# Sheet1.net
KiCad netlist of a schematic drawn in Altium Designer
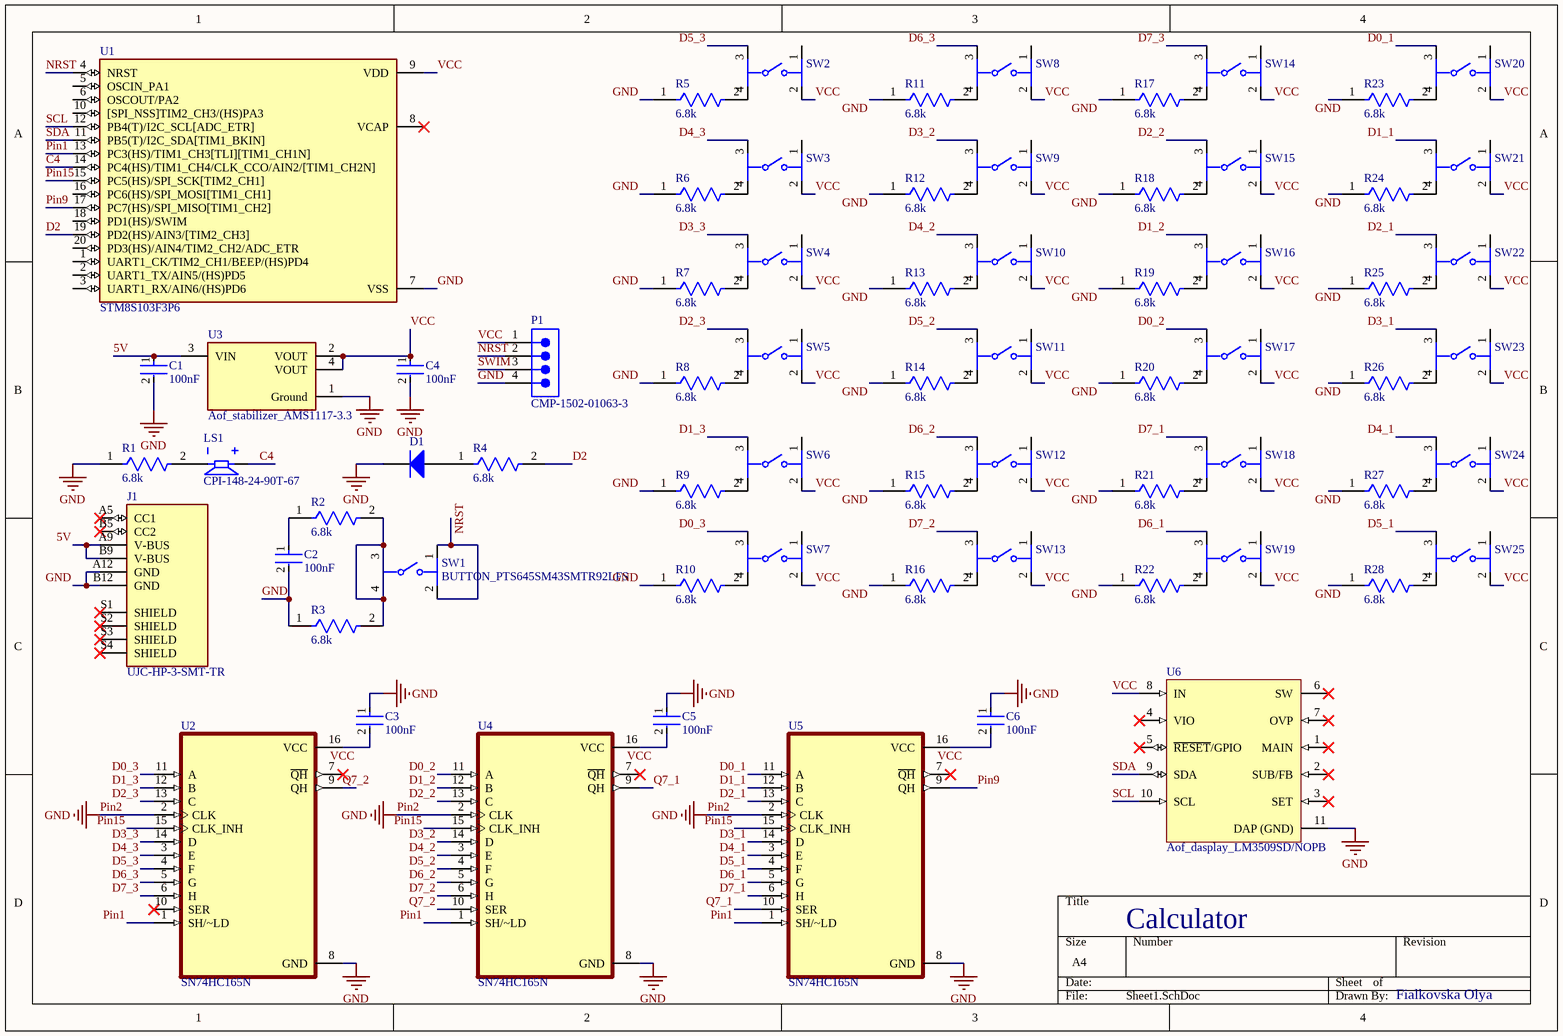
[diagram p0: Sheet1.SchDoc]

(export (version "E")
  (design (tool "Eeschema 10.0.6"))
  (components
    (comp (ref "C1")
      (value "100nF")
      (footprint "FP-GRM033-0_03-MFG")
      (description "10V 100nF X5R ±10% 0201 Multilayer Ceramic Capacitors MLCC - SMD/SMT ROHS")
      (fields (field (name "TOLERANCE") "10%") (field (name "Comment") "Aof_GRM033R61A104KE15D"))
      (libsource (lib "National Technical University of Ukraine Igor Sikorsky Kyiv Polytechnic Institute- Educator Program") (part "b4654b650e69147ec39a6b967a45e02"))
    )
    (comp (ref "C2")
      (value "100nF")
      (footprint "FP-GRM033-0_03-MFG")
      (description "10V 100nF X5R ±10% 0201 Multilayer Ceramic Capacitors MLCC - SMD/SMT ROHS")
      (fields (field (name "TOLERANCE") "10%") (field (name "Comment") "Aof_GRM033R61A104KE15D"))
      (libsource (lib "National Technical University of Ukraine Igor Sikorsky Kyiv Polytechnic Institute- Educator Program") (part "b4654b650e69147ec39a6b967a45e02"))
    )
    (comp (ref "C3")
      (value "100nF")
      (footprint "FP-GRM033-0_03-MFG")
      (description "10V 100nF X5R ±10% 0201 Multilayer Ceramic Capacitors MLCC - SMD/SMT ROHS")
      (fields (field (name "TOLERANCE") "10%") (field (name "Comment") "Aof_GRM033R61A104KE15D"))
      (libsource (lib "National Technical University of Ukraine Igor Sikorsky Kyiv Polytechnic Institute- Educator Program") (part "b4654b650e69147ec39a6b967a45e02"))
    )
    (comp (ref "C4")
      (value "100nF")
      (footprint "FP-GRM033-0_03-MFG")
      (description "10V 100nF X5R ±10% 0201 Multilayer Ceramic Capacitors MLCC - SMD/SMT ROHS")
      (fields (field (name "TOLERANCE") "10%") (field (name "Comment") "Aof_GRM033R61A104KE15D"))
      (libsource (lib "National Technical University of Ukraine Igor Sikorsky Kyiv Polytechnic Institute- Educator Program") (part "b4654b650e69147ec39a6b967a45e02"))
    )
    (comp (ref "C5")
      (value "100nF")
      (footprint "FP-GRM033-0_03-MFG")
      (description "10V 100nF X5R ±10% 0201 Multilayer Ceramic Capacitors MLCC - SMD/SMT ROHS")
      (fields (field (name "TOLERANCE") "10%") (field (name "Comment") "Aof_GRM033R61A104KE15D"))
      (libsource (lib "National Technical University of Ukraine Igor Sikorsky Kyiv Polytechnic Institute- Educator Program") (part "b4654b650e69147ec39a6b967a45e02"))
    )
    (comp (ref "C6")
      (value "100nF")
      (footprint "FP-GRM033-0_03-MFG")
      (description "10V 100nF X5R ±10% 0201 Multilayer Ceramic Capacitors MLCC - SMD/SMT ROHS")
      (fields (field (name "TOLERANCE") "10%") (field (name "Comment") "Aof_GRM033R61A104KE15D"))
      (libsource (lib "National Technical University of Ukraine Igor Sikorsky Kyiv Polytechnic Institute- Educator Program") (part "b4654b650e69147ec39a6b967a45e02"))
    )
    (comp (ref "D1") (value "Diode") (libsource (lib "Simulation Generic Components") (part "Diode")))
    (comp (ref "J1")
      (value "UJC-HP-3-SMT-TR")
      (footprint "CUI_UJC-HP-3-SMT-TR")
      (libsource (lib "National Technical University of Ukraine Igor Sikorsky Kyiv Polytechnic Institute- Educator Program") (part "UJC-HP-3-SMT-TR"))
    )
    (comp (ref "LS1")
      (value "CPI-148-24-90T-67")
      (footprint "XDCR_CPI-148-24-90T-67")
      (fields (field (name "MF") "Same Sky"))
      (libsource (lib "National Technical University of Ukraine Igor Sikorsky Kyiv Polytechnic Institute- Educator Program") (part "CPI-148-24-90T-67"))
    )
    (comp (ref "P1")
      (value "CMP-1502-01063-3")
      (footprint "61300411021")
      (libsource (lib "National Technical University of Ukraine Igor Sikorsky Kyiv Polytechnic Institute- Educator Program") (part "CMP-1502-01063-3"))
    )
    (comp (ref "R1")
      (value "6.8k")
      (footprint "FP-RK73HW3A-IPC_A")
      (fields (field (name "TOLERANCE") "1%") (field (name "Comment") "Aof_RK73HW3ATTE6801F"))
      (libsource (lib "National Technical University of Ukraine Igor Sikorsky Kyiv Polytechnic Institute- Educator Program") (part "1029c3af85768c4190bb7ad29bc67b5"))
    )
    (comp (ref "R2")
      (value "6.8k")
      (footprint "FP-RK73HW3A-IPC_A")
      (fields (field (name "TOLERANCE") "1%") (field (name "Comment") "Aof_RK73HW3ATTE6801F"))
      (libsource (lib "National Technical University of Ukraine Igor Sikorsky Kyiv Polytechnic Institute- Educator Program") (part "1029c3af85768c4190bb7ad29bc67b5"))
    )
    (comp (ref "R3")
      (value "6.8k")
      (footprint "FP-RK73HW3A-IPC_A")
      (fields (field (name "TOLERANCE") "1%") (field (name "Comment") "Aof_RK73HW3ATTE6801F"))
      (libsource (lib "National Technical University of Ukraine Igor Sikorsky Kyiv Polytechnic Institute- Educator Program") (part "1029c3af85768c4190bb7ad29bc67b5"))
    )
    (comp (ref "R4")
      (value "6.8k")
      (footprint "FP-RK73HW3A-IPC_A")
      (fields (field (name "TOLERANCE") "1%") (field (name "Comment") "Aof_RK73HW3ATTE6801F"))
      (libsource (lib "National Technical University of Ukraine Igor Sikorsky Kyiv Polytechnic Institute- Educator Program") (part "1029c3af85768c4190bb7ad29bc67b5"))
    )
    (comp (ref "R5")
      (value "6.8k")
      (footprint "FP-RK73HW3A-IPC_A")
      (fields (field (name "TOLERANCE") "1%") (field (name "Comment") "Aof_RK73HW3ATTE6801F"))
      (libsource (lib "National Technical University of Ukraine Igor Sikorsky Kyiv Polytechnic Institute- Educator Program") (part "1029c3af85768c4190bb7ad29bc67b5"))
    )
    (comp (ref "R6")
      (value "6.8k")
      (footprint "FP-RK73HW3A-IPC_A")
      (fields (field (name "TOLERANCE") "1%") (field (name "Comment") "Aof_RK73HW3ATTE6801F"))
      (libsource (lib "National Technical University of Ukraine Igor Sikorsky Kyiv Polytechnic Institute- Educator Program") (part "1029c3af85768c4190bb7ad29bc67b5"))
    )
    (comp (ref "R7")
      (value "6.8k")
      (footprint "FP-RK73HW3A-IPC_A")
      (fields (field (name "TOLERANCE") "1%") (field (name "Comment") "Aof_RK73HW3ATTE6801F"))
      (libsource (lib "National Technical University of Ukraine Igor Sikorsky Kyiv Polytechnic Institute- Educator Program") (part "1029c3af85768c4190bb7ad29bc67b5"))
    )
    (comp (ref "R8")
      (value "6.8k")
      (footprint "FP-RK73HW3A-IPC_A")
      (fields (field (name "TOLERANCE") "1%") (field (name "Comment") "Aof_RK73HW3ATTE6801F"))
      (libsource (lib "National Technical University of Ukraine Igor Sikorsky Kyiv Polytechnic Institute- Educator Program") (part "1029c3af85768c4190bb7ad29bc67b5"))
    )
    (comp (ref "R9")
      (value "6.8k")
      (footprint "FP-RK73HW3A-IPC_A")
      (fields (field (name "TOLERANCE") "1%") (field (name "Comment") "Aof_RK73HW3ATTE6801F"))
      (libsource (lib "National Technical University of Ukraine Igor Sikorsky Kyiv Polytechnic Institute- Educator Program") (part "1029c3af85768c4190bb7ad29bc67b5"))
    )
    (comp (ref "R10")
      (value "6.8k")
      (footprint "FP-RK73HW3A-IPC_A")
      (fields (field (name "TOLERANCE") "1%") (field (name "Comment") "Aof_RK73HW3ATTE6801F"))
      (libsource (lib "National Technical University of Ukraine Igor Sikorsky Kyiv Polytechnic Institute- Educator Program") (part "1029c3af85768c4190bb7ad29bc67b5"))
    )
    (comp (ref "R11")
      (value "6.8k")
      (footprint "FP-RK73HW3A-IPC_A")
      (fields (field (name "TOLERANCE") "1%") (field (name "Comment") "Aof_RK73HW3ATTE6801F"))
      (libsource (lib "National Technical University of Ukraine Igor Sikorsky Kyiv Polytechnic Institute- Educator Program") (part "1029c3af85768c4190bb7ad29bc67b5"))
    )
    (comp (ref "R12")
      (value "6.8k")
      (footprint "FP-RK73HW3A-IPC_A")
      (fields (field (name "TOLERANCE") "1%") (field (name "Comment") "Aof_RK73HW3ATTE6801F"))
      (libsource (lib "National Technical University of Ukraine Igor Sikorsky Kyiv Polytechnic Institute- Educator Program") (part "1029c3af85768c4190bb7ad29bc67b5"))
    )
    (comp (ref "R13")
      (value "6.8k")
      (footprint "FP-RK73HW3A-IPC_A")
      (fields (field (name "TOLERANCE") "1%") (field (name "Comment") "Aof_RK73HW3ATTE6801F"))
      (libsource (lib "National Technical University of Ukraine Igor Sikorsky Kyiv Polytechnic Institute- Educator Program") (part "1029c3af85768c4190bb7ad29bc67b5"))
    )
    (comp (ref "R14")
      (value "6.8k")
      (footprint "FP-RK73HW3A-IPC_A")
      (fields (field (name "TOLERANCE") "1%") (field (name "Comment") "Aof_RK73HW3ATTE6801F"))
      (libsource (lib "National Technical University of Ukraine Igor Sikorsky Kyiv Polytechnic Institute- Educator Program") (part "1029c3af85768c4190bb7ad29bc67b5"))
    )
    (comp (ref "R15")
      (value "6.8k")
      (footprint "FP-RK73HW3A-IPC_A")
      (fields (field (name "TOLERANCE") "1%") (field (name "Comment") "Aof_RK73HW3ATTE6801F"))
      (libsource (lib "National Technical University of Ukraine Igor Sikorsky Kyiv Polytechnic Institute- Educator Program") (part "1029c3af85768c4190bb7ad29bc67b5"))
    )
    (comp (ref "R16")
      (value "6.8k")
      (footprint "FP-RK73HW3A-IPC_A")
      (fields (field (name "TOLERANCE") "1%") (field (name "Comment") "Aof_RK73HW3ATTE6801F"))
      (libsource (lib "National Technical University of Ukraine Igor Sikorsky Kyiv Polytechnic Institute- Educator Program") (part "1029c3af85768c4190bb7ad29bc67b5"))
    )
    (comp (ref "R17")
      (value "6.8k")
      (footprint "FP-RK73HW3A-IPC_A")
      (fields (field (name "TOLERANCE") "1%") (field (name "Comment") "Aof_RK73HW3ATTE6801F"))
      (libsource (lib "National Technical University of Ukraine Igor Sikorsky Kyiv Polytechnic Institute- Educator Program") (part "1029c3af85768c4190bb7ad29bc67b5"))
    )
    (comp (ref "R18")
      (value "6.8k")
      (footprint "FP-RK73HW3A-IPC_A")
      (fields (field (name "TOLERANCE") "1%") (field (name "Comment") "Aof_RK73HW3ATTE6801F"))
      (libsource (lib "National Technical University of Ukraine Igor Sikorsky Kyiv Polytechnic Institute- Educator Program") (part "1029c3af85768c4190bb7ad29bc67b5"))
    )
    (comp (ref "R19")
      (value "6.8k")
      (footprint "FP-RK73HW3A-IPC_A")
      (fields (field (name "TOLERANCE") "1%") (field (name "Comment") "Aof_RK73HW3ATTE6801F"))
      (libsource (lib "National Technical University of Ukraine Igor Sikorsky Kyiv Polytechnic Institute- Educator Program") (part "1029c3af85768c4190bb7ad29bc67b5"))
    )
    (comp (ref "R20")
      (value "6.8k")
      (footprint "FP-RK73HW3A-IPC_A")
      (fields (field (name "TOLERANCE") "1%") (field (name "Comment") "Aof_RK73HW3ATTE6801F"))
      (libsource (lib "National Technical University of Ukraine Igor Sikorsky Kyiv Polytechnic Institute- Educator Program") (part "1029c3af85768c4190bb7ad29bc67b5"))
    )
    (comp (ref "R21")
      (value "6.8k")
      (footprint "FP-RK73HW3A-IPC_A")
      (fields (field (name "TOLERANCE") "1%") (field (name "Comment") "Aof_RK73HW3ATTE6801F"))
      (libsource (lib "National Technical University of Ukraine Igor Sikorsky Kyiv Polytechnic Institute- Educator Program") (part "1029c3af85768c4190bb7ad29bc67b5"))
    )
    (comp (ref "R22")
      (value "6.8k")
      (footprint "FP-RK73HW3A-IPC_A")
      (fields (field (name "TOLERANCE") "1%") (field (name "Comment") "Aof_RK73HW3ATTE6801F"))
      (libsource (lib "National Technical University of Ukraine Igor Sikorsky Kyiv Polytechnic Institute- Educator Program") (part "1029c3af85768c4190bb7ad29bc67b5"))
    )
    (comp (ref "R23")
      (value "6.8k")
      (footprint "FP-RK73HW3A-IPC_A")
      (fields (field (name "TOLERANCE") "1%") (field (name "Comment") "Aof_RK73HW3ATTE6801F"))
      (libsource (lib "National Technical University of Ukraine Igor Sikorsky Kyiv Polytechnic Institute- Educator Program") (part "1029c3af85768c4190bb7ad29bc67b5"))
    )
    (comp (ref "R24")
      (value "6.8k")
      (footprint "FP-RK73HW3A-IPC_A")
      (fields (field (name "TOLERANCE") "1%") (field (name "Comment") "Aof_RK73HW3ATTE6801F"))
      (libsource (lib "National Technical University of Ukraine Igor Sikorsky Kyiv Polytechnic Institute- Educator Program") (part "1029c3af85768c4190bb7ad29bc67b5"))
    )
    (comp (ref "R25")
      (value "6.8k")
      (footprint "FP-RK73HW3A-IPC_A")
      (fields (field (name "TOLERANCE") "1%") (field (name "Comment") "Aof_RK73HW3ATTE6801F"))
      (libsource (lib "National Technical University of Ukraine Igor Sikorsky Kyiv Polytechnic Institute- Educator Program") (part "1029c3af85768c4190bb7ad29bc67b5"))
    )
    (comp (ref "R26")
      (value "6.8k")
      (footprint "FP-RK73HW3A-IPC_A")
      (fields (field (name "TOLERANCE") "1%") (field (name "Comment") "Aof_RK73HW3ATTE6801F"))
      (libsource (lib "National Technical University of Ukraine Igor Sikorsky Kyiv Polytechnic Institute- Educator Program") (part "1029c3af85768c4190bb7ad29bc67b5"))
    )
    (comp (ref "R27")
      (value "6.8k")
      (footprint "FP-RK73HW3A-IPC_A")
      (fields (field (name "TOLERANCE") "1%") (field (name "Comment") "Aof_RK73HW3ATTE6801F"))
      (libsource (lib "National Technical University of Ukraine Igor Sikorsky Kyiv Polytechnic Institute- Educator Program") (part "1029c3af85768c4190bb7ad29bc67b5"))
    )
    (comp (ref "R28")
      (value "6.8k")
      (footprint "FP-RK73HW3A-IPC_A")
      (fields (field (name "TOLERANCE") "1%") (field (name "Comment") "Aof_RK73HW3ATTE6801F"))
      (libsource (lib "National Technical University of Ukraine Igor Sikorsky Kyiv Polytechnic Institute- Educator Program") (part "1029c3af85768c4190bb7ad29bc67b5"))
    )
    (comp (ref "SW1")
      (value "BUTTON_PTS645SM43SMTR92LFS")
      (footprint "FP-PTS645SM43SMTR92LFS-MFG")
      (libsource (lib "National Technical University of Ukraine Igor Sikorsky Kyiv Polytechnic Institute- Educator Program") (part "1adf0dd01260c80cf25a44bfd6b99ba"))
    )
    (comp (ref "SW2")
      (value "BUTTON_PTS645SM43SMTR92LFS")
      (footprint "FP-PTS645SM43SMTR92LFS-MFG")
      (libsource (lib "National Technical University of Ukraine Igor Sikorsky Kyiv Polytechnic Institute- Educator Program") (part "1adf0dd01260c80cf25a44bfd6b99ba"))
    )
    (comp (ref "SW3")
      (value "BUTTON_PTS645SM43SMTR92LFS")
      (footprint "FP-PTS645SM43SMTR92LFS-MFG")
      (libsource (lib "National Technical University of Ukraine Igor Sikorsky Kyiv Polytechnic Institute- Educator Program") (part "1adf0dd01260c80cf25a44bfd6b99ba"))
    )
    (comp (ref "SW4")
      (value "BUTTON_PTS645SM43SMTR92LFS")
      (footprint "FP-PTS645SM43SMTR92LFS-MFG")
      (libsource (lib "National Technical University of Ukraine Igor Sikorsky Kyiv Polytechnic Institute- Educator Program") (part "1adf0dd01260c80cf25a44bfd6b99ba"))
    )
    (comp (ref "SW5")
      (value "BUTTON_PTS645SM43SMTR92LFS")
      (footprint "FP-PTS645SM43SMTR92LFS-MFG")
      (libsource (lib "National Technical University of Ukraine Igor Sikorsky Kyiv Polytechnic Institute- Educator Program") (part "1adf0dd01260c80cf25a44bfd6b99ba"))
    )
    (comp (ref "SW6")
      (value "BUTTON_PTS645SM43SMTR92LFS")
      (footprint "FP-PTS645SM43SMTR92LFS-MFG")
      (libsource (lib "National Technical University of Ukraine Igor Sikorsky Kyiv Polytechnic Institute- Educator Program") (part "1adf0dd01260c80cf25a44bfd6b99ba"))
    )
    (comp (ref "SW7")
      (value "BUTTON_PTS645SM43SMTR92LFS")
      (footprint "FP-PTS645SM43SMTR92LFS-MFG")
      (libsource (lib "National Technical University of Ukraine Igor Sikorsky Kyiv Polytechnic Institute- Educator Program") (part "1adf0dd01260c80cf25a44bfd6b99ba"))
    )
    (comp (ref "SW8")
      (value "BUTTON_PTS645SM43SMTR92LFS")
      (footprint "FP-PTS645SM43SMTR92LFS-MFG")
      (libsource (lib "National Technical University of Ukraine Igor Sikorsky Kyiv Polytechnic Institute- Educator Program") (part "1adf0dd01260c80cf25a44bfd6b99ba"))
    )
    (comp (ref "SW9")
      (value "BUTTON_PTS645SM43SMTR92LFS")
      (footprint "FP-PTS645SM43SMTR92LFS-MFG")
      (libsource (lib "National Technical University of Ukraine Igor Sikorsky Kyiv Polytechnic Institute- Educator Program") (part "1adf0dd01260c80cf25a44bfd6b99ba"))
    )
    (comp (ref "SW10")
      (value "BUTTON_PTS645SM43SMTR92LFS")
      (footprint "FP-PTS645SM43SMTR92LFS-MFG")
      (libsource (lib "National Technical University of Ukraine Igor Sikorsky Kyiv Polytechnic Institute- Educator Program") (part "1adf0dd01260c80cf25a44bfd6b99ba"))
    )
    (comp (ref "SW11")
      (value "BUTTON_PTS645SM43SMTR92LFS")
      (footprint "FP-PTS645SM43SMTR92LFS-MFG")
      (libsource (lib "National Technical University of Ukraine Igor Sikorsky Kyiv Polytechnic Institute- Educator Program") (part "1adf0dd01260c80cf25a44bfd6b99ba"))
    )
    (comp (ref "SW12")
      (value "BUTTON_PTS645SM43SMTR92LFS")
      (footprint "FP-PTS645SM43SMTR92LFS-MFG")
      (libsource (lib "National Technical University of Ukraine Igor Sikorsky Kyiv Polytechnic Institute- Educator Program") (part "1adf0dd01260c80cf25a44bfd6b99ba"))
    )
    (comp (ref "SW13")
      (value "BUTTON_PTS645SM43SMTR92LFS")
      (footprint "FP-PTS645SM43SMTR92LFS-MFG")
      (libsource (lib "National Technical University of Ukraine Igor Sikorsky Kyiv Polytechnic Institute- Educator Program") (part "1adf0dd01260c80cf25a44bfd6b99ba"))
    )
    (comp (ref "SW14")
      (value "BUTTON_PTS645SM43SMTR92LFS")
      (footprint "FP-PTS645SM43SMTR92LFS-MFG")
      (libsource (lib "National Technical University of Ukraine Igor Sikorsky Kyiv Polytechnic Institute- Educator Program") (part "1adf0dd01260c80cf25a44bfd6b99ba"))
    )
    (comp (ref "SW15")
      (value "BUTTON_PTS645SM43SMTR92LFS")
      (footprint "FP-PTS645SM43SMTR92LFS-MFG")
      (libsource (lib "National Technical University of Ukraine Igor Sikorsky Kyiv Polytechnic Institute- Educator Program") (part "1adf0dd01260c80cf25a44bfd6b99ba"))
    )
    (comp (ref "SW16")
      (value "BUTTON_PTS645SM43SMTR92LFS")
      (footprint "FP-PTS645SM43SMTR92LFS-MFG")
      (libsource (lib "National Technical University of Ukraine Igor Sikorsky Kyiv Polytechnic Institute- Educator Program") (part "1adf0dd01260c80cf25a44bfd6b99ba"))
    )
    (comp (ref "SW17")
      (value "BUTTON_PTS645SM43SMTR92LFS")
      (footprint "FP-PTS645SM43SMTR92LFS-MFG")
      (libsource (lib "National Technical University of Ukraine Igor Sikorsky Kyiv Polytechnic Institute- Educator Program") (part "1adf0dd01260c80cf25a44bfd6b99ba"))
    )
    (comp (ref "SW18")
      (value "BUTTON_PTS645SM43SMTR92LFS")
      (footprint "FP-PTS645SM43SMTR92LFS-MFG")
      (libsource (lib "National Technical University of Ukraine Igor Sikorsky Kyiv Polytechnic Institute- Educator Program") (part "1adf0dd01260c80cf25a44bfd6b99ba"))
    )
    (comp (ref "SW19")
      (value "BUTTON_PTS645SM43SMTR92LFS")
      (footprint "FP-PTS645SM43SMTR92LFS-MFG")
      (libsource (lib "National Technical University of Ukraine Igor Sikorsky Kyiv Polytechnic Institute- Educator Program") (part "1adf0dd01260c80cf25a44bfd6b99ba"))
    )
    (comp (ref "SW20")
      (value "BUTTON_PTS645SM43SMTR92LFS")
      (footprint "FP-PTS645SM43SMTR92LFS-MFG")
      (libsource (lib "National Technical University of Ukraine Igor Sikorsky Kyiv Polytechnic Institute- Educator Program") (part "1adf0dd01260c80cf25a44bfd6b99ba"))
    )
    (comp (ref "SW21")
      (value "BUTTON_PTS645SM43SMTR92LFS")
      (footprint "FP-PTS645SM43SMTR92LFS-MFG")
      (libsource (lib "National Technical University of Ukraine Igor Sikorsky Kyiv Polytechnic Institute- Educator Program") (part "1adf0dd01260c80cf25a44bfd6b99ba"))
    )
    (comp (ref "SW22")
      (value "BUTTON_PTS645SM43SMTR92LFS")
      (footprint "FP-PTS645SM43SMTR92LFS-MFG")
      (libsource (lib "National Technical University of Ukraine Igor Sikorsky Kyiv Polytechnic Institute- Educator Program") (part "1adf0dd01260c80cf25a44bfd6b99ba"))
    )
    (comp (ref "SW23")
      (value "BUTTON_PTS645SM43SMTR92LFS")
      (footprint "FP-PTS645SM43SMTR92LFS-MFG")
      (libsource (lib "National Technical University of Ukraine Igor Sikorsky Kyiv Polytechnic Institute- Educator Program") (part "1adf0dd01260c80cf25a44bfd6b99ba"))
    )
    (comp (ref "SW24")
      (value "BUTTON_PTS645SM43SMTR92LFS")
      (footprint "FP-PTS645SM43SMTR92LFS-MFG")
      (libsource (lib "National Technical University of Ukraine Igor Sikorsky Kyiv Polytechnic Institute- Educator Program") (part "1adf0dd01260c80cf25a44bfd6b99ba"))
    )
    (comp (ref "SW25")
      (value "BUTTON_PTS645SM43SMTR92LFS")
      (footprint "FP-PTS645SM43SMTR92LFS-MFG")
      (libsource (lib "National Technical University of Ukraine Igor Sikorsky Kyiv Polytechnic Institute- Educator Program") (part "1adf0dd01260c80cf25a44bfd6b99ba"))
    )
    (comp (ref "U1")
      (value "STM8S103F3P6")
      (footprint "SOP65P640X120-20N")
      (description "STM8 series Microcontroller IC 8-Bit 16MHz 8KB (8K x 8) FLASH 20-TSSOP")
      (fields (field (name "MF") "STMicroelectronics"))
      (libsource (lib "National Technical University of Ukraine Igor Sikorsky Kyiv Polytechnic Institute- Educator Program") (part "STM8S103F3P6"))
    )
    (comp (ref "U2")
      (value "SN74HC165N")
      (footprint "DIP794W45P254L1969H508Q16")
      (description "8-Bit Parallel-Load Shift Registers")
      (fields (field (name "MF") "Texas Instruments"))
      (libsource (lib "National Technical University of Ukraine Igor Sikorsky Kyiv Polytechnic Institute- Educator Program") (part "SN74HC165N"))
    )
    (comp (ref "U3")
      (value "Aof_stabilizer_AMS1117-3.3")
      (footprint "FP-AMS1117-IPC_B")
      (libsource (lib "National Technical University of Ukraine Igor Sikorsky Kyiv Polytechnic Institute- Educator Program") (part "8bdbb5f8e77002000e30dd2845d0354"))
    )
    (comp (ref "U4")
      (value "SN74HC165N")
      (footprint "DIP794W45P254L1969H508Q16")
      (description "8-Bit Parallel-Load Shift Registers")
      (fields (field (name "MF") "Texas Instruments"))
      (libsource (lib "National Technical University of Ukraine Igor Sikorsky Kyiv Polytechnic Institute- Educator Program") (part "SN74HC165N"))
    )
    (comp (ref "U5")
      (value "SN74HC165N")
      (footprint "DIP794W45P254L1969H508Q16")
      (description "8-Bit Parallel-Load Shift Registers")
      (fields (field (name "MF") "Texas Instruments"))
      (libsource (lib "National Technical University of Ukraine Igor Sikorsky Kyiv Polytechnic Institute- Educator Program") (part "SN74HC165N"))
    )
    (comp (ref "U6")
      (value "Aof_dasplay_LM3509SD/NOPB")
      (footprint "DSC0010A_V")
      (description "Tape & Reel (TR) LM3509 Step-Up (Boost) I2C led driver 3mm 440muA 5.5V 1.25MHz")
      (libsource (lib "National Technical University of Ukraine Igor Sikorsky Kyiv Polytechnic Institute- Educator Program") (part "IN-LEDD-LM3509-11"))
    )
  )
  (nets
    (net (code "1") (name "/5V") (class "Default")
      (node (ref "C1") (pin "1") (pinfunction "1_1") (pintype "passive"))
      (node (ref "J1") (pin "A9") (pinfunction "V-BUS_A9") (pintype "power_in"))
      (node (ref "J1") (pin "B9") (pinfunction "V-BUS_B9") (pintype "power_in"))
      (node (ref "U3") (pin "3") (pinfunction "VIN_3") (pintype "power_in"))
    )
    (net (code "2") (name "/C4") (class "Default")
      (node (ref "LS1") (pin "P") (pinfunction "P_P") (pintype "passive"))
      (node (ref "U1") (pin "14") (pinfunction "PC4(HS)/TIM1_CH4/CLK_CCO/AIN2/[TIM1_CH2N]_14") (pintype "bidirectional"))
    )
    (net (code "3") (name "/D0_1") (class "Default")
      (node (ref "SW20") (pin "3") (pinfunction "3_3") (pintype "passive"))
      (node (ref "U5") (pin "11") (pinfunction "A_11") (pintype "input"))
    )
    (net (code "4") (name "/D0_2") (class "Default")
      (node (ref "SW17") (pin "3") (pinfunction "3_3") (pintype "passive"))
      (node (ref "U4") (pin "11") (pinfunction "A_11") (pintype "input"))
    )
    (net (code "5") (name "/D0_3") (class "Default")
      (node (ref "SW7") (pin "3") (pinfunction "3_3") (pintype "passive"))
      (node (ref "U2") (pin "11") (pinfunction "A_11") (pintype "input"))
    )
    (net (code "6") (name "/D1_1") (class "Default")
      (node (ref "SW21") (pin "3") (pinfunction "3_3") (pintype "passive"))
      (node (ref "U5") (pin "12") (pinfunction "B_12") (pintype "input"))
    )
    (net (code "7") (name "/D1_2") (class "Default")
      (node (ref "SW16") (pin "3") (pinfunction "3_3") (pintype "passive"))
      (node (ref "U4") (pin "12") (pinfunction "B_12") (pintype "input"))
    )
    (net (code "8") (name "/D1_3") (class "Default")
      (node (ref "SW6") (pin "3") (pinfunction "3_3") (pintype "passive"))
      (node (ref "U2") (pin "12") (pinfunction "B_12") (pintype "input"))
    )
    (net (code "9") (name "/D2") (class "Default")
      (node (ref "R4") (pin "2") (pinfunction "2_2") (pintype "passive"))
      (node (ref "U1") (pin "19") (pinfunction "PD2(HS)/AIN3/[TIM2_CH3]_19") (pintype "bidirectional"))
    )
    (net (code "10") (name "/D2_1") (class "Default")
      (node (ref "SW22") (pin "3") (pinfunction "3_3") (pintype "passive"))
      (node (ref "U5") (pin "13") (pinfunction "C_13") (pintype "input"))
    )
    (net (code "11") (name "/D2_2") (class "Default")
      (node (ref "SW15") (pin "3") (pinfunction "3_3") (pintype "passive"))
      (node (ref "U4") (pin "13") (pinfunction "C_13") (pintype "input"))
    )
    (net (code "12") (name "/D2_3") (class "Default")
      (node (ref "SW5") (pin "3") (pinfunction "3_3") (pintype "passive"))
      (node (ref "U2") (pin "13") (pinfunction "C_13") (pintype "input"))
    )
    (net (code "13") (name "/D3_1") (class "Default")
      (node (ref "SW23") (pin "3") (pinfunction "3_3") (pintype "passive"))
      (node (ref "U5") (pin "14") (pinfunction "D_14") (pintype "input"))
    )
    (net (code "14") (name "/D3_2") (class "Default")
      (node (ref "SW9") (pin "3") (pinfunction "3_3") (pintype "passive"))
      (node (ref "U4") (pin "14") (pinfunction "D_14") (pintype "input"))
    )
    (net (code "15") (name "/D3_3") (class "Default")
      (node (ref "SW4") (pin "3") (pinfunction "3_3") (pintype "passive"))
      (node (ref "U2") (pin "14") (pinfunction "D_14") (pintype "input"))
    )
    (net (code "16") (name "/D4_1") (class "Default")
      (node (ref "SW24") (pin "3") (pinfunction "3_3") (pintype "passive"))
      (node (ref "U5") (pin "3") (pinfunction "E_3") (pintype "input"))
    )
    (net (code "17") (name "/D4_2") (class "Default")
      (node (ref "SW10") (pin "3") (pinfunction "3_3") (pintype "passive"))
      (node (ref "U4") (pin "3") (pinfunction "E_3") (pintype "input"))
    )
    (net (code "18") (name "/D4_3") (class "Default")
      (node (ref "SW3") (pin "3") (pinfunction "3_3") (pintype "passive"))
      (node (ref "U2") (pin "3") (pinfunction "E_3") (pintype "input"))
    )
    (net (code "19") (name "/D5_1") (class "Default")
      (node (ref "SW25") (pin "3") (pinfunction "3_3") (pintype "passive"))
      (node (ref "U5") (pin "4") (pinfunction "F_4") (pintype "input"))
    )
    (net (code "20") (name "/D5_2") (class "Default")
      (node (ref "SW11") (pin "3") (pinfunction "3_3") (pintype "passive"))
      (node (ref "U4") (pin "4") (pinfunction "F_4") (pintype "input"))
    )
    (net (code "21") (name "/D5_3") (class "Default")
      (node (ref "SW2") (pin "3") (pinfunction "3_3") (pintype "passive"))
      (node (ref "U2") (pin "4") (pinfunction "F_4") (pintype "input"))
    )
    (net (code "22") (name "/D6_1") (class "Default")
      (node (ref "SW19") (pin "3") (pinfunction "3_3") (pintype "passive"))
      (node (ref "U5") (pin "5") (pinfunction "G_5") (pintype "input"))
    )
    (net (code "23") (name "/D6_2") (class "Default")
      (node (ref "SW12") (pin "3") (pinfunction "3_3") (pintype "passive"))
      (node (ref "U4") (pin "5") (pinfunction "G_5") (pintype "input"))
    )
    (net (code "24") (name "/D6_3") (class "Default")
      (node (ref "SW8") (pin "3") (pinfunction "3_3") (pintype "passive"))
      (node (ref "U2") (pin "5") (pinfunction "G_5") (pintype "input"))
    )
    (net (code "25") (name "/D7_1") (class "Default")
      (node (ref "SW18") (pin "3") (pinfunction "3_3") (pintype "passive"))
      (node (ref "U5") (pin "6") (pinfunction "H_6") (pintype "input"))
    )
    (net (code "26") (name "/D7_2") (class "Default")
      (node (ref "SW13") (pin "3") (pinfunction "3_3") (pintype "passive"))
      (node (ref "U4") (pin "6") (pinfunction "H_6") (pintype "input"))
    )
    (net (code "27") (name "/D7_3") (class "Default")
      (node (ref "SW14") (pin "3") (pinfunction "3_3") (pintype "passive"))
      (node (ref "U2") (pin "6") (pinfunction "H_6") (pintype "input"))
    )
    (net (code "28") (name "/NRST") (class "Default")
      (node (ref "P1") (pin "2") (pinfunction "2_2") (pintype "passive"))
      (node (ref "SW1") (pin "1") (pinfunction "1_1") (pintype "passive"))
      (node (ref "SW1") (pin "2") (pinfunction "2_2") (pintype "passive"))
      (node (ref "U1") (pin "4") (pinfunction "NRST_4") (pintype "bidirectional"))
    )
    (net (code "29") (name "/Pin1") (class "Default")
      (node (ref "U1") (pin "13") (pinfunction "PC3(HS)/TIM1_CH3[TLI][TIM1_CH1N]_13") (pintype "bidirectional"))
      (node (ref "U2") (pin "1") (pinfunction "SH/~LD_1") (pintype "input"))
      (node (ref "U4") (pin "1") (pinfunction "SH/~LD_1") (pintype "input"))
      (node (ref "U5") (pin "1") (pinfunction "SH/~LD_1") (pintype "input"))
    )
    (net (code "30") (name "/Pin9") (class "Default")
      (node (ref "U1") (pin "17") (pinfunction "PC7(HS)/SPI_MISO[TIM1_CH2]_17") (pintype "bidirectional"))
      (node (ref "U5") (pin "9") (pinfunction "QH_9") (pintype "output"))
    )
    (net (code "31") (name "/Pin15") (class "Default")
      (node (ref "U1") (pin "15") (pinfunction "PC5(HS)/SPI_SCK[TIM2_CH1]_15") (pintype "bidirectional"))
      (node (ref "U2") (pin "15") (pinfunction "CLK_INH_15") (pintype "input"))
      (node (ref "U4") (pin "15") (pinfunction "CLK_INH_15") (pintype "input"))
      (node (ref "U5") (pin "15") (pinfunction "CLK_INH_15") (pintype "input"))
    )
    (net (code "32") (name "/Q7_1") (class "Default")
      (node (ref "U4") (pin "9") (pinfunction "QH_9") (pintype "output"))
      (node (ref "U5") (pin "10") (pinfunction "SER_10") (pintype "input"))
    )
    (net (code "33") (name "/Q7_2") (class "Default")
      (node (ref "U2") (pin "9") (pinfunction "QH_9") (pintype "output"))
      (node (ref "U4") (pin "10") (pinfunction "SER_10") (pintype "input"))
    )
    (net (code "34") (name "/SCL") (class "Default")
      (node (ref "U1") (pin "12") (pinfunction "PB4(T)/I2C_SCL[ADC_ETR]_12") (pintype "bidirectional"))
      (node (ref "U6") (pin "10") (pinfunction "SCL_10") (pintype "input"))
    )
    (net (code "35") (name "/SDA") (class "Default")
      (node (ref "U1") (pin "11") (pinfunction "PB5(T)/I2C_SDA[TIM1_BKIN]_11") (pintype "bidirectional"))
      (node (ref "U6") (pin "9") (pinfunction "SDA_9") (pintype "bidirectional"))
    )
    (net (code "36") (name "/SWIM") (class "Default")
      (node (ref "P1") (pin "3") (pinfunction "3_3") (pintype "passive"))
    )
    (net (code "37") (name "/VCC") (class "Default")
      (node (ref "C3") (pin "2") (pinfunction "2_2") (pintype "passive"))
      (node (ref "C4") (pin "1") (pinfunction "1_1") (pintype "passive"))
      (node (ref "C5") (pin "2") (pinfunction "2_2") (pintype "passive"))
      (node (ref "C6") (pin "2") (pinfunction "2_2") (pintype "passive"))
      (node (ref "P1") (pin "1") (pinfunction "1_1") (pintype "passive"))
      (node (ref "SW10") (pin "2") (pinfunction "2_2") (pintype "passive"))
      (node (ref "SW11") (pin "2") (pinfunction "2_2") (pintype "passive"))
      (node (ref "SW12") (pin "2") (pinfunction "2_2") (pintype "passive"))
      (node (ref "SW13") (pin "2") (pinfunction "2_2") (pintype "passive"))
      (node (ref "SW14") (pin "2") (pinfunction "2_2") (pintype "passive"))
      (node (ref "SW15") (pin "2") (pinfunction "2_2") (pintype "passive"))
      (node (ref "SW16") (pin "2") (pinfunction "2_2") (pintype "passive"))
      (node (ref "SW17") (pin "2") (pinfunction "2_2") (pintype "passive"))
      (node (ref "SW18") (pin "2") (pinfunction "2_2") (pintype "passive"))
      (node (ref "SW19") (pin "2") (pinfunction "2_2") (pintype "passive"))
      (node (ref "SW2") (pin "2") (pinfunction "2_2") (pintype "passive"))
      (node (ref "SW20") (pin "2") (pinfunction "2_2") (pintype "passive"))
      (node (ref "SW21") (pin "2") (pinfunction "2_2") (pintype "passive"))
      (node (ref "SW22") (pin "2") (pinfunction "2_2") (pintype "passive"))
      (node (ref "SW23") (pin "2") (pinfunction "2_2") (pintype "passive"))
      (node (ref "SW24") (pin "2") (pinfunction "2_2") (pintype "passive"))
      (node (ref "SW25") (pin "2") (pinfunction "2_2") (pintype "passive"))
      (node (ref "SW3") (pin "2") (pinfunction "2_2") (pintype "passive"))
      (node (ref "SW4") (pin "2") (pinfunction "2_2") (pintype "passive"))
      (node (ref "SW5") (pin "2") (pinfunction "2_2") (pintype "passive"))
      (node (ref "SW6") (pin "2") (pinfunction "2_2") (pintype "passive"))
      (node (ref "SW7") (pin "2") (pinfunction "2_2") (pintype "passive"))
      (node (ref "SW8") (pin "2") (pinfunction "2_2") (pintype "passive"))
      (node (ref "SW9") (pin "2") (pinfunction "2_2") (pintype "passive"))
      (node (ref "U1") (pin "9") (pinfunction "VDD_9") (pintype "power_in"))
      (node (ref "U2") (pin "16") (pinfunction "VCC_16") (pintype "power_in"))
      (node (ref "U3") (pin "2") (pinfunction "VOUT_2") (pintype "passive"))
      (node (ref "U3") (pin "4") (pinfunction "VOUT_4") (pintype "passive"))
      (node (ref "U4") (pin "16") (pinfunction "VCC_16") (pintype "power_in"))
      (node (ref "U5") (pin "16") (pinfunction "VCC_16") (pintype "power_in"))
      (node (ref "U6") (pin "8") (pinfunction "IN_8") (pintype "input"))
    )
    (net (code "38") (name "GND") (class "Default")
      (node (ref "C1") (pin "2") (pinfunction "2_2") (pintype "passive"))
      (node (ref "C2") (pin "2") (pinfunction "2_2") (pintype "passive"))
      (node (ref "C3") (pin "1") (pinfunction "1_1") (pintype "passive"))
      (node (ref "C4") (pin "2") (pinfunction "2_2") (pintype "passive"))
      (node (ref "C5") (pin "1") (pinfunction "1_1") (pintype "passive"))
      (node (ref "C6") (pin "1") (pinfunction "1_1") (pintype "passive"))
      (node (ref "D1") (pin "2") (pinfunction "K_2") (pintype "passive"))
      (node (ref "J1") (pin "A12") (pinfunction "GND_A12") (pintype "power_in"))
      (node (ref "J1") (pin "B12") (pinfunction "GND_B12") (pintype "power_in"))
      (node (ref "P1") (pin "4") (pinfunction "4_4") (pintype "passive"))
      (node (ref "R1") (pin "1") (pinfunction "1_1") (pintype "passive"))
      (node (ref "R10") (pin "1") (pinfunction "1_1") (pintype "passive"))
      (node (ref "R11") (pin "1") (pinfunction "1_1") (pintype "passive"))
      (node (ref "R12") (pin "1") (pinfunction "1_1") (pintype "passive"))
      (node (ref "R13") (pin "1") (pinfunction "1_1") (pintype "passive"))
      (node (ref "R14") (pin "1") (pinfunction "1_1") (pintype "passive"))
      (node (ref "R15") (pin "1") (pinfunction "1_1") (pintype "passive"))
      (node (ref "R16") (pin "1") (pinfunction "1_1") (pintype "passive"))
      (node (ref "R17") (pin "1") (pinfunction "1_1") (pintype "passive"))
      (node (ref "R18") (pin "1") (pinfunction "1_1") (pintype "passive"))
      (node (ref "R19") (pin "1") (pinfunction "1_1") (pintype "passive"))
      (node (ref "R20") (pin "1") (pinfunction "1_1") (pintype "passive"))
      (node (ref "R21") (pin "1") (pinfunction "1_1") (pintype "passive"))
      (node (ref "R22") (pin "1") (pinfunction "1_1") (pintype "passive"))
      (node (ref "R23") (pin "1") (pinfunction "1_1") (pintype "passive"))
      (node (ref "R24") (pin "1") (pinfunction "1_1") (pintype "passive"))
      (node (ref "R25") (pin "1") (pinfunction "1_1") (pintype "passive"))
      (node (ref "R26") (pin "1") (pinfunction "1_1") (pintype "passive"))
      (node (ref "R27") (pin "1") (pinfunction "1_1") (pintype "passive"))
      (node (ref "R28") (pin "1") (pinfunction "1_1") (pintype "passive"))
      (node (ref "R3") (pin "1") (pinfunction "1_1") (pintype "passive"))
      (node (ref "R5") (pin "1") (pinfunction "1_1") (pintype "passive"))
      (node (ref "R6") (pin "1") (pinfunction "1_1") (pintype "passive"))
      (node (ref "R7") (pin "1") (pinfunction "1_1") (pintype "passive"))
      (node (ref "R8") (pin "1") (pinfunction "1_1") (pintype "passive"))
      (node (ref "R9") (pin "1") (pinfunction "1_1") (pintype "passive"))
      (node (ref "U1") (pin "7") (pinfunction "VSS_7") (pintype "power_in"))
      (node (ref "U2") (pin "2") (pinfunction "CLK_2") (pintype "input"))
      (node (ref "U2") (pin "8") (pinfunction "GND_8") (pintype "power_in"))
      (node (ref "U3") (pin "1") (pinfunction "Ground_1") (pintype "power_in"))
      (node (ref "U4") (pin "2") (pinfunction "CLK_2") (pintype "input"))
      (node (ref "U4") (pin "8") (pinfunction "GND_8") (pintype "power_in"))
      (node (ref "U5") (pin "2") (pinfunction "CLK_2") (pintype "input"))
      (node (ref "U5") (pin "8") (pinfunction "GND_8") (pintype "power_in"))
      (node (ref "U6") (pin "11") (pinfunction "DAP_(GND)_11") (pintype "power_in"))
    )
    (net (code "39") (name "Net-(C2-Pad1)") (class "Default")
      (node (ref "C2") (pin "1") (pinfunction "1_1") (pintype "passive"))
      (node (ref "R2") (pin "1") (pinfunction "1_1") (pintype "passive"))
    )
    (net (code "40") (name "Net-(D1-A)") (class "Default")
      (node (ref "D1") (pin "1") (pinfunction "A_1") (pintype "passive"))
      (node (ref "R4") (pin "1") (pinfunction "1_1") (pintype "passive"))
    )
    (net (code "41") (name "Net-(LS1-PadN)") (class "Default")
      (node (ref "LS1") (pin "N") (pinfunction "N_N") (pintype "passive"))
      (node (ref "R1") (pin "2") (pinfunction "2_2") (pintype "passive"))
    )
    (net (code "42") (name "Net-(R2-Pad2)") (class "Default")
      (node (ref "R2") (pin "2") (pinfunction "2_2") (pintype "passive"))
      (node (ref "R3") (pin "2") (pinfunction "2_2") (pintype "passive"))
      (node (ref "SW1") (pin "3") (pinfunction "3_3") (pintype "passive"))
      (node (ref "SW1") (pin "4") (pinfunction "4_4") (pintype "passive"))
    )
    (net (code "43") (name "Net-(R5-Pad2)") (class "Default")
      (node (ref "R5") (pin "2") (pinfunction "2_2") (pintype "passive"))
      (node (ref "SW2") (pin "4") (pinfunction "4_4") (pintype "passive"))
    )
    (net (code "44") (name "Net-(R6-Pad2)") (class "Default")
      (node (ref "R6") (pin "2") (pinfunction "2_2") (pintype "passive"))
      (node (ref "SW3") (pin "4") (pinfunction "4_4") (pintype "passive"))
    )
    (net (code "45") (name "Net-(R7-Pad2)") (class "Default")
      (node (ref "R7") (pin "2") (pinfunction "2_2") (pintype "passive"))
      (node (ref "SW4") (pin "4") (pinfunction "4_4") (pintype "passive"))
    )
    (net (code "46") (name "Net-(R8-Pad2)") (class "Default")
      (node (ref "R8") (pin "2") (pinfunction "2_2") (pintype "passive"))
      (node (ref "SW5") (pin "4") (pinfunction "4_4") (pintype "passive"))
    )
    (net (code "47") (name "Net-(R9-Pad2)") (class "Default")
      (node (ref "R9") (pin "2") (pinfunction "2_2") (pintype "passive"))
      (node (ref "SW6") (pin "4") (pinfunction "4_4") (pintype "passive"))
    )
    (net (code "48") (name "Net-(R10-Pad2)") (class "Default")
      (node (ref "R10") (pin "2") (pinfunction "2_2") (pintype "passive"))
      (node (ref "SW7") (pin "4") (pinfunction "4_4") (pintype "passive"))
    )
    (net (code "49") (name "Net-(R11-Pad2)") (class "Default")
      (node (ref "R11") (pin "2") (pinfunction "2_2") (pintype "passive"))
      (node (ref "SW8") (pin "4") (pinfunction "4_4") (pintype "passive"))
    )
    (net (code "50") (name "Net-(R12-Pad2)") (class "Default")
      (node (ref "R12") (pin "2") (pinfunction "2_2") (pintype "passive"))
      (node (ref "SW9") (pin "4") (pinfunction "4_4") (pintype "passive"))
    )
    (net (code "51") (name "Net-(R13-Pad2)") (class "Default")
      (node (ref "R13") (pin "2") (pinfunction "2_2") (pintype "passive"))
      (node (ref "SW10") (pin "4") (pinfunction "4_4") (pintype "passive"))
    )
    (net (code "52") (name "Net-(R14-Pad2)") (class "Default")
      (node (ref "R14") (pin "2") (pinfunction "2_2") (pintype "passive"))
      (node (ref "SW11") (pin "4") (pinfunction "4_4") (pintype "passive"))
    )
    (net (code "53") (name "Net-(R15-Pad2)") (class "Default")
      (node (ref "R15") (pin "2") (pinfunction "2_2") (pintype "passive"))
      (node (ref "SW12") (pin "4") (pinfunction "4_4") (pintype "passive"))
    )
    (net (code "54") (name "Net-(R16-Pad2)") (class "Default")
      (node (ref "R16") (pin "2") (pinfunction "2_2") (pintype "passive"))
      (node (ref "SW13") (pin "4") (pinfunction "4_4") (pintype "passive"))
    )
    (net (code "55") (name "Net-(R17-Pad2)") (class "Default")
      (node (ref "R17") (pin "2") (pinfunction "2_2") (pintype "passive"))
      (node (ref "SW14") (pin "4") (pinfunction "4_4") (pintype "passive"))
    )
    (net (code "56") (name "Net-(R18-Pad2)") (class "Default")
      (node (ref "R18") (pin "2") (pinfunction "2_2") (pintype "passive"))
      (node (ref "SW15") (pin "4") (pinfunction "4_4") (pintype "passive"))
    )
    (net (code "57") (name "Net-(R19-Pad2)") (class "Default")
      (node (ref "R19") (pin "2") (pinfunction "2_2") (pintype "passive"))
      (node (ref "SW16") (pin "4") (pinfunction "4_4") (pintype "passive"))
    )
    (net (code "58") (name "Net-(R20-Pad2)") (class "Default")
      (node (ref "R20") (pin "2") (pinfunction "2_2") (pintype "passive"))
      (node (ref "SW17") (pin "4") (pinfunction "4_4") (pintype "passive"))
    )
    (net (code "59") (name "Net-(R21-Pad2)") (class "Default")
      (node (ref "R21") (pin "2") (pinfunction "2_2") (pintype "passive"))
      (node (ref "SW18") (pin "4") (pinfunction "4_4") (pintype "passive"))
    )
    (net (code "60") (name "Net-(R22-Pad2)") (class "Default")
      (node (ref "R22") (pin "2") (pinfunction "2_2") (pintype "passive"))
      (node (ref "SW19") (pin "4") (pinfunction "4_4") (pintype "passive"))
    )
    (net (code "61") (name "Net-(R23-Pad2)") (class "Default")
      (node (ref "R23") (pin "2") (pinfunction "2_2") (pintype "passive"))
      (node (ref "SW20") (pin "4") (pinfunction "4_4") (pintype "passive"))
    )
    (net (code "62") (name "Net-(R24-Pad2)") (class "Default")
      (node (ref "R24") (pin "2") (pinfunction "2_2") (pintype "passive"))
      (node (ref "SW21") (pin "4") (pinfunction "4_4") (pintype "passive"))
    )
    (net (code "63") (name "Net-(R25-Pad2)") (class "Default")
      (node (ref "R25") (pin "2") (pinfunction "2_2") (pintype "passive"))
      (node (ref "SW22") (pin "4") (pinfunction "4_4") (pintype "passive"))
    )
    (net (code "64") (name "Net-(R26-Pad2)") (class "Default")
      (node (ref "R26") (pin "2") (pinfunction "2_2") (pintype "passive"))
      (node (ref "SW23") (pin "4") (pinfunction "4_4") (pintype "passive"))
    )
    (net (code "65") (name "Net-(R27-Pad2)") (class "Default")
      (node (ref "R27") (pin "2") (pinfunction "2_2") (pintype "passive"))
      (node (ref "SW24") (pin "4") (pinfunction "4_4") (pintype "passive"))
    )
    (net (code "66") (name "Net-(R28-Pad2)") (class "Default")
      (node (ref "R28") (pin "2") (pinfunction "2_2") (pintype "passive"))
      (node (ref "SW25") (pin "4") (pinfunction "4_4") (pintype "passive"))
    )
    (net (code "67") (name "unconnected-(J1-CC1-PadA5)") (class "Default")
      (node (ref "J1") (pin "A5") (pinfunction "CC1_A5") (pintype "bidirectional+no_connect"))
    )
    (net (code "68") (name "unconnected-(J1-CC2-PadB5)") (class "Default")
      (node (ref "J1") (pin "B5") (pinfunction "CC2_B5") (pintype "bidirectional+no_connect"))
    )
    (net (code "69") (name "unconnected-(J1-SHIELD-PadS1)") (class "Default")
      (node (ref "J1") (pin "S1") (pinfunction "SHIELD_S1") (pintype "passive+no_connect"))
    )
    (net (code "70") (name "unconnected-(J1-SHIELD-PadS2)") (class "Default")
      (node (ref "J1") (pin "S2") (pinfunction "SHIELD_S2") (pintype "passive+no_connect"))
    )
    (net (code "71") (name "unconnected-(J1-SHIELD-PadS3)") (class "Default")
      (node (ref "J1") (pin "S3") (pinfunction "SHIELD_S3") (pintype "passive+no_connect"))
    )
    (net (code "72") (name "unconnected-(J1-SHIELD-PadS4)") (class "Default")
      (node (ref "J1") (pin "S4") (pinfunction "SHIELD_S4") (pintype "passive+no_connect"))
    )
    (net (code "73") (name "unconnected-(SW2-Pad1)") (class "Default")
      (node (ref "SW2") (pin "1") (pinfunction "1_1") (pintype "passive"))
    )
    (net (code "74") (name "unconnected-(SW3-Pad1)") (class "Default")
      (node (ref "SW3") (pin "1") (pinfunction "1_1") (pintype "passive"))
    )
    (net (code "75") (name "unconnected-(SW4-Pad1)") (class "Default")
      (node (ref "SW4") (pin "1") (pinfunction "1_1") (pintype "passive"))
    )
    (net (code "76") (name "unconnected-(SW5-Pad1)") (class "Default")
      (node (ref "SW5") (pin "1") (pinfunction "1_1") (pintype "passive"))
    )
    (net (code "77") (name "unconnected-(SW6-Pad1)") (class "Default")
      (node (ref "SW6") (pin "1") (pinfunction "1_1") (pintype "passive"))
    )
    (net (code "78") (name "unconnected-(SW7-Pad1)") (class "Default")
      (node (ref "SW7") (pin "1") (pinfunction "1_1") (pintype "passive"))
    )
    (net (code "79") (name "unconnected-(SW8-Pad1)") (class "Default")
      (node (ref "SW8") (pin "1") (pinfunction "1_1") (pintype "passive"))
    )
    (net (code "80") (name "unconnected-(SW9-Pad1)") (class "Default")
      (node (ref "SW9") (pin "1") (pinfunction "1_1") (pintype "passive"))
    )
    (net (code "81") (name "unconnected-(SW10-Pad1)") (class "Default")
      (node (ref "SW10") (pin "1") (pinfunction "1_1") (pintype "passive"))
    )
    (net (code "82") (name "unconnected-(SW11-Pad1)") (class "Default")
      (node (ref "SW11") (pin "1") (pinfunction "1_1") (pintype "passive"))
    )
    (net (code "83") (name "unconnected-(SW12-Pad1)") (class "Default")
      (node (ref "SW12") (pin "1") (pinfunction "1_1") (pintype "passive"))
    )
    (net (code "84") (name "unconnected-(SW13-Pad1)") (class "Default")
      (node (ref "SW13") (pin "1") (pinfunction "1_1") (pintype "passive"))
    )
    (net (code "85") (name "unconnected-(SW14-Pad1)") (class "Default")
      (node (ref "SW14") (pin "1") (pinfunction "1_1") (pintype "passive"))
    )
    (net (code "86") (name "unconnected-(SW15-Pad1)") (class "Default")
      (node (ref "SW15") (pin "1") (pinfunction "1_1") (pintype "passive"))
    )
    (net (code "87") (name "unconnected-(SW16-Pad1)") (class "Default")
      (node (ref "SW16") (pin "1") (pinfunction "1_1") (pintype "passive"))
    )
    (net (code "88") (name "unconnected-(SW17-Pad1)") (class "Default")
      (node (ref "SW17") (pin "1") (pinfunction "1_1") (pintype "passive"))
    )
    (net (code "89") (name "unconnected-(SW18-Pad1)") (class "Default")
      (node (ref "SW18") (pin "1") (pinfunction "1_1") (pintype "passive"))
    )
    (net (code "90") (name "unconnected-(SW19-Pad1)") (class "Default")
      (node (ref "SW19") (pin "1") (pinfunction "1_1") (pintype "passive"))
    )
    (net (code "91") (name "unconnected-(SW20-Pad1)") (class "Default")
      (node (ref "SW20") (pin "1") (pinfunction "1_1") (pintype "passive"))
    )
    (net (code "92") (name "unconnected-(SW21-Pad1)") (class "Default")
      (node (ref "SW21") (pin "1") (pinfunction "1_1") (pintype "passive"))
    )
    (net (code "93") (name "unconnected-(SW22-Pad1)") (class "Default")
      (node (ref "SW22") (pin "1") (pinfunction "1_1") (pintype "passive"))
    )
    (net (code "94") (name "unconnected-(SW23-Pad1)") (class "Default")
      (node (ref "SW23") (pin "1") (pinfunction "1_1") (pintype "passive"))
    )
    (net (code "95") (name "unconnected-(SW24-Pad1)") (class "Default")
      (node (ref "SW24") (pin "1") (pinfunction "1_1") (pintype "passive"))
    )
    (net (code "96") (name "unconnected-(SW25-Pad1)") (class "Default")
      (node (ref "SW25") (pin "1") (pinfunction "1_1") (pintype "passive"))
    )
    (net (code "97") (name "unconnected-(U1-OSCIN_PA1-Pad5)") (class "Default")
      (node (ref "U1") (pin "5") (pinfunction "OSCIN_PA1_5") (pintype "bidirectional"))
    )
    (net (code "98") (name "unconnected-(U1-OSCOUT{slash}PA2-Pad6)") (class "Default")
      (node (ref "U1") (pin "6") (pinfunction "OSCOUT/PA2_6") (pintype "bidirectional"))
    )
    (net (code "99") (name "unconnected-(U1-PC6(HS){slash}SPI_MOSI[TIM1_CH1]-Pad16)") (class "Default")
      (node (ref "U1") (pin "16") (pinfunction "PC6(HS)/SPI_MOSI[TIM1_CH1]_16") (pintype "bidirectional"))
    )
    (net (code "100") (name "unconnected-(U1-PD1(HS){slash}SWIM-Pad18)") (class "Default")
      (node (ref "U1") (pin "18") (pinfunction "PD1(HS)/SWIM_18") (pintype "bidirectional"))
    )
    (net (code "101") (name "unconnected-(U1-PD3(HS){slash}AIN4{slash}TIM2_CH2{slash}ADC_ETR-Pad20)") (class "Default")
      (node (ref "U1") (pin "20") (pinfunction "PD3(HS)/AIN4/TIM2_CH2/ADC_ETR_20") (pintype "bidirectional"))
    )
    (net (code "102") (name "unconnected-(U1-UART1_CK{slash}TIM2_CH1{slash}BEEP{slash}(HS)PD4-Pad1)") (class "Default")
      (node (ref "U1") (pin "1") (pinfunction "UART1_CK/TIM2_CH1/BEEP/(HS)PD4_1") (pintype "bidirectional"))
    )
    (net (code "103") (name "unconnected-(U1-UART1_RX{slash}AIN6{slash}(HS)PD6-Pad3)") (class "Default")
      (node (ref "U1") (pin "3") (pinfunction "UART1_RX/AIN6/(HS)PD6_3") (pintype "bidirectional"))
    )
    (net (code "104") (name "unconnected-(U1-UART1_TX{slash}AIN5{slash}(HS)PD5-Pad2)") (class "Default")
      (node (ref "U1") (pin "2") (pinfunction "UART1_TX/AIN5/(HS)PD5_2") (pintype "bidirectional"))
    )
    (net (code "105") (name "unconnected-(U1-VCAP-Pad8)") (class "Default")
      (node (ref "U1") (pin "8") (pinfunction "VCAP_8") (pintype "passive+no_connect"))
    )
    (net (code "106") (name "unconnected-(U1-[SPI_NSS]TIM2_CH3{slash}(HS)PA3-Pad10)") (class "Default")
      (node (ref "U1") (pin "10") (pinfunction "[SPI_NSS]TIM2_CH3/(HS)PA3_10") (pintype "bidirectional"))
    )
    (net (code "107") (name "unconnected-(U2-SER-Pad10)") (class "Default")
      (node (ref "U2") (pin "10") (pinfunction "SER_10") (pintype "input+no_connect"))
    )
    (net (code "108") (name "unconnected-(U2-~{QH}-Pad7)") (class "Default")
      (node (ref "U2") (pin "7") (pinfunction "~{QH}_7") (pintype "output+no_connect"))
    )
    (net (code "109") (name "unconnected-(U4-~{QH}-Pad7)") (class "Default")
      (node (ref "U4") (pin "7") (pinfunction "~{QH}_7") (pintype "output+no_connect"))
    )
    (net (code "110") (name "unconnected-(U5-~{QH}-Pad7)") (class "Default")
      (node (ref "U5") (pin "7") (pinfunction "~{QH}_7") (pintype "output+no_connect"))
    )
    (net (code "111") (name "unconnected-(U6-MAIN-Pad1)") (class "Default")
      (node (ref "U6") (pin "1") (pinfunction "MAIN_1") (pintype "input+no_connect"))
    )
    (net (code "112") (name "unconnected-(U6-OVP-Pad7)") (class "Default")
      (node (ref "U6") (pin "7") (pinfunction "OVP_7") (pintype "input+no_connect"))
    )
    (net (code "113") (name "unconnected-(U6-SET-Pad3)") (class "Default")
      (node (ref "U6") (pin "3") (pinfunction "SET_3") (pintype "input+no_connect"))
    )
    (net (code "114") (name "unconnected-(U6-SUB{slash}FB-Pad2)") (class "Default")
      (node (ref "U6") (pin "2") (pinfunction "SUB/FB_2") (pintype "input+no_connect"))
    )
    (net (code "115") (name "unconnected-(U6-SW-Pad6)") (class "Default")
      (node (ref "U6") (pin "6") (pinfunction "SW_6") (pintype "power_in+no_connect"))
    )
    (net (code "116") (name "unconnected-(U6-VIO-Pad4)") (class "Default")
      (node (ref "U6") (pin "4") (pinfunction "VIO_4") (pintype "input+no_connect"))
    )
    (net (code "117") (name "unconnected-(U6-~{RESET}{slash}GPIO-Pad5)") (class "Default")
      (node (ref "U6") (pin "5") (pinfunction "~{RESET}/GPIO_5") (pintype "bidirectional+no_connect"))
    )
  )
)
